# uno_sensor_shield.net
KiCad netlist of a schematic drawn in EAGLE
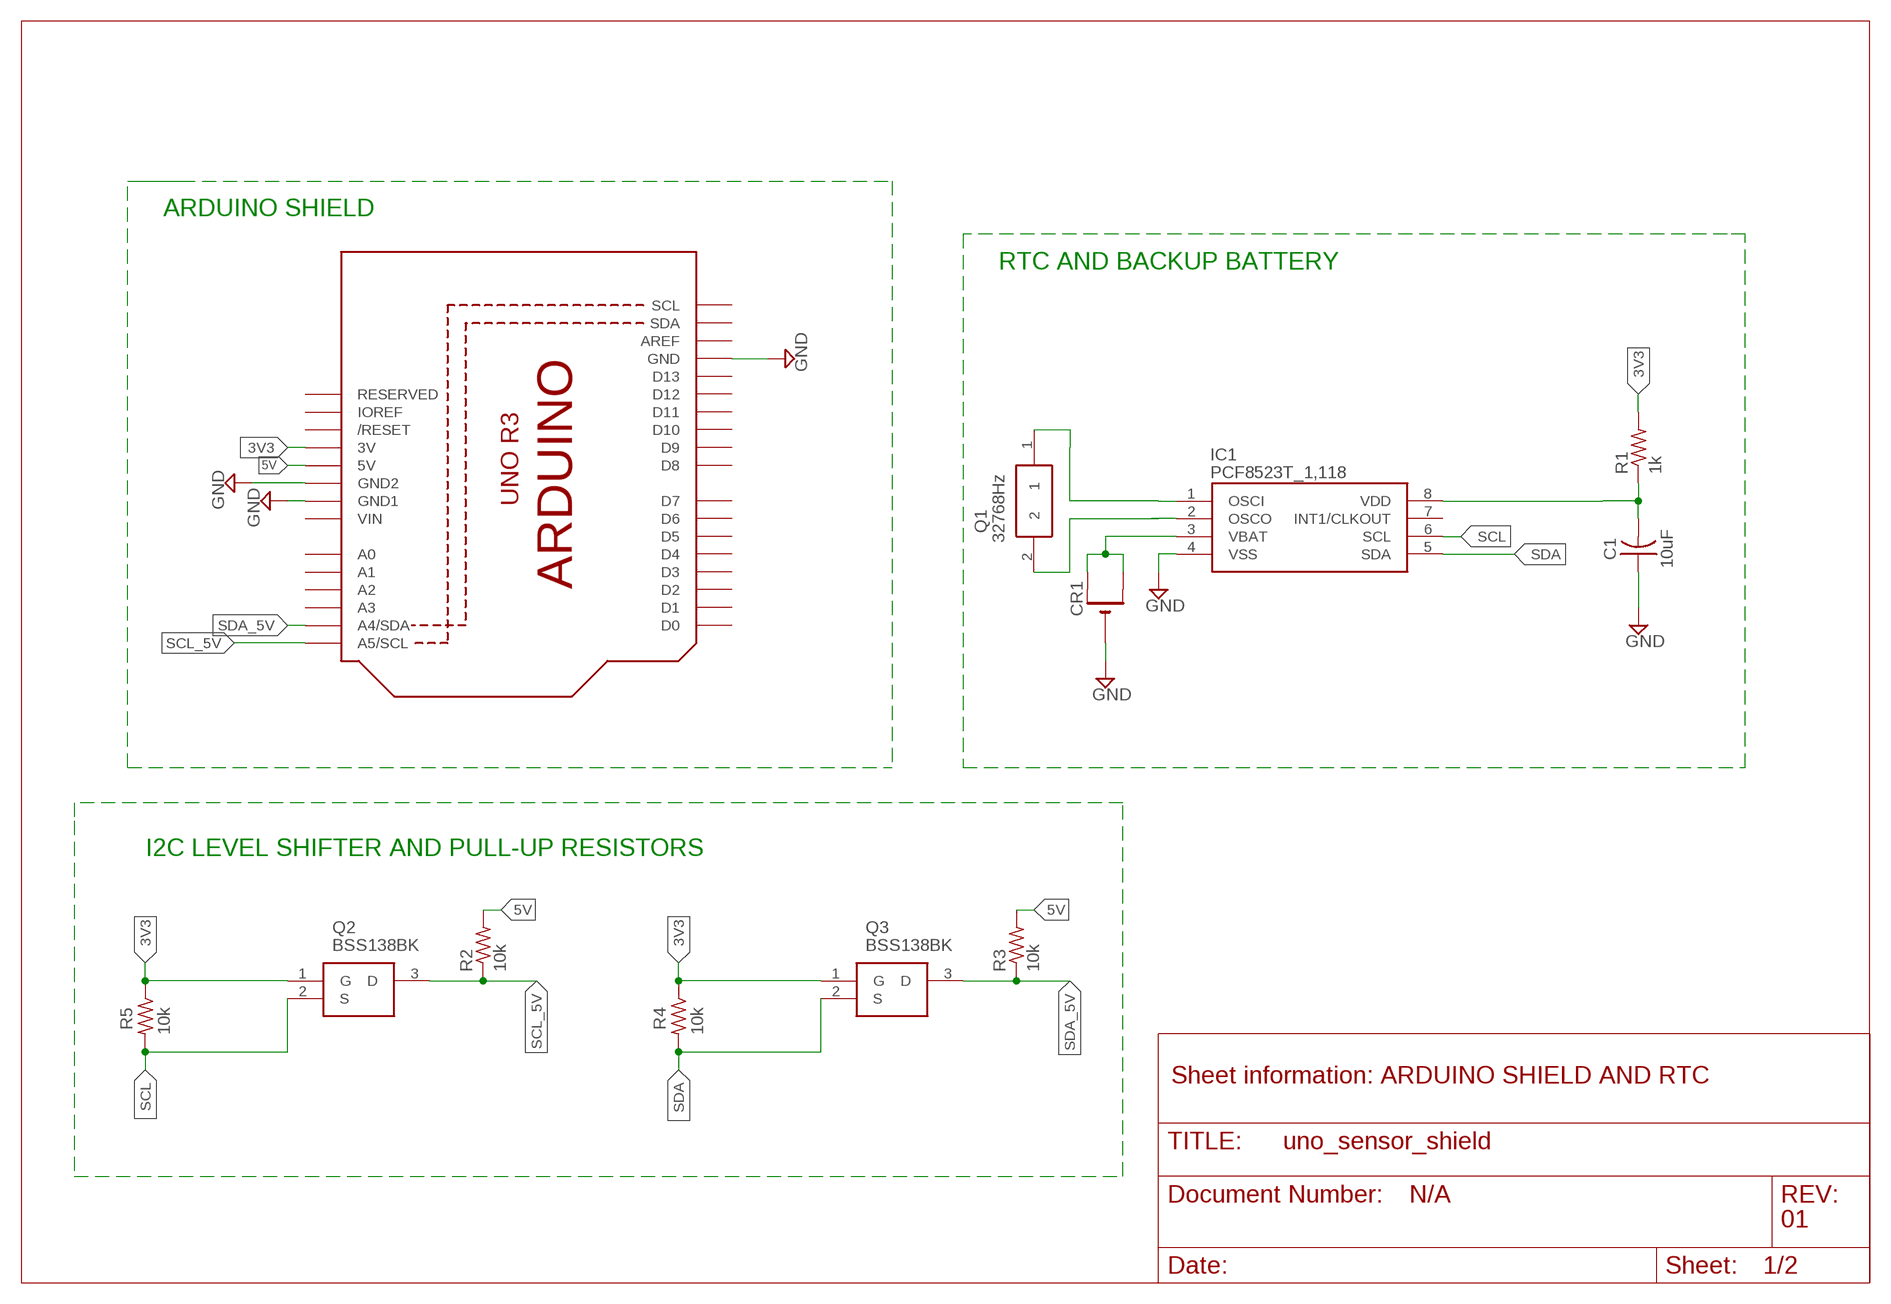
[diagram p0: schematic, sheet 1]
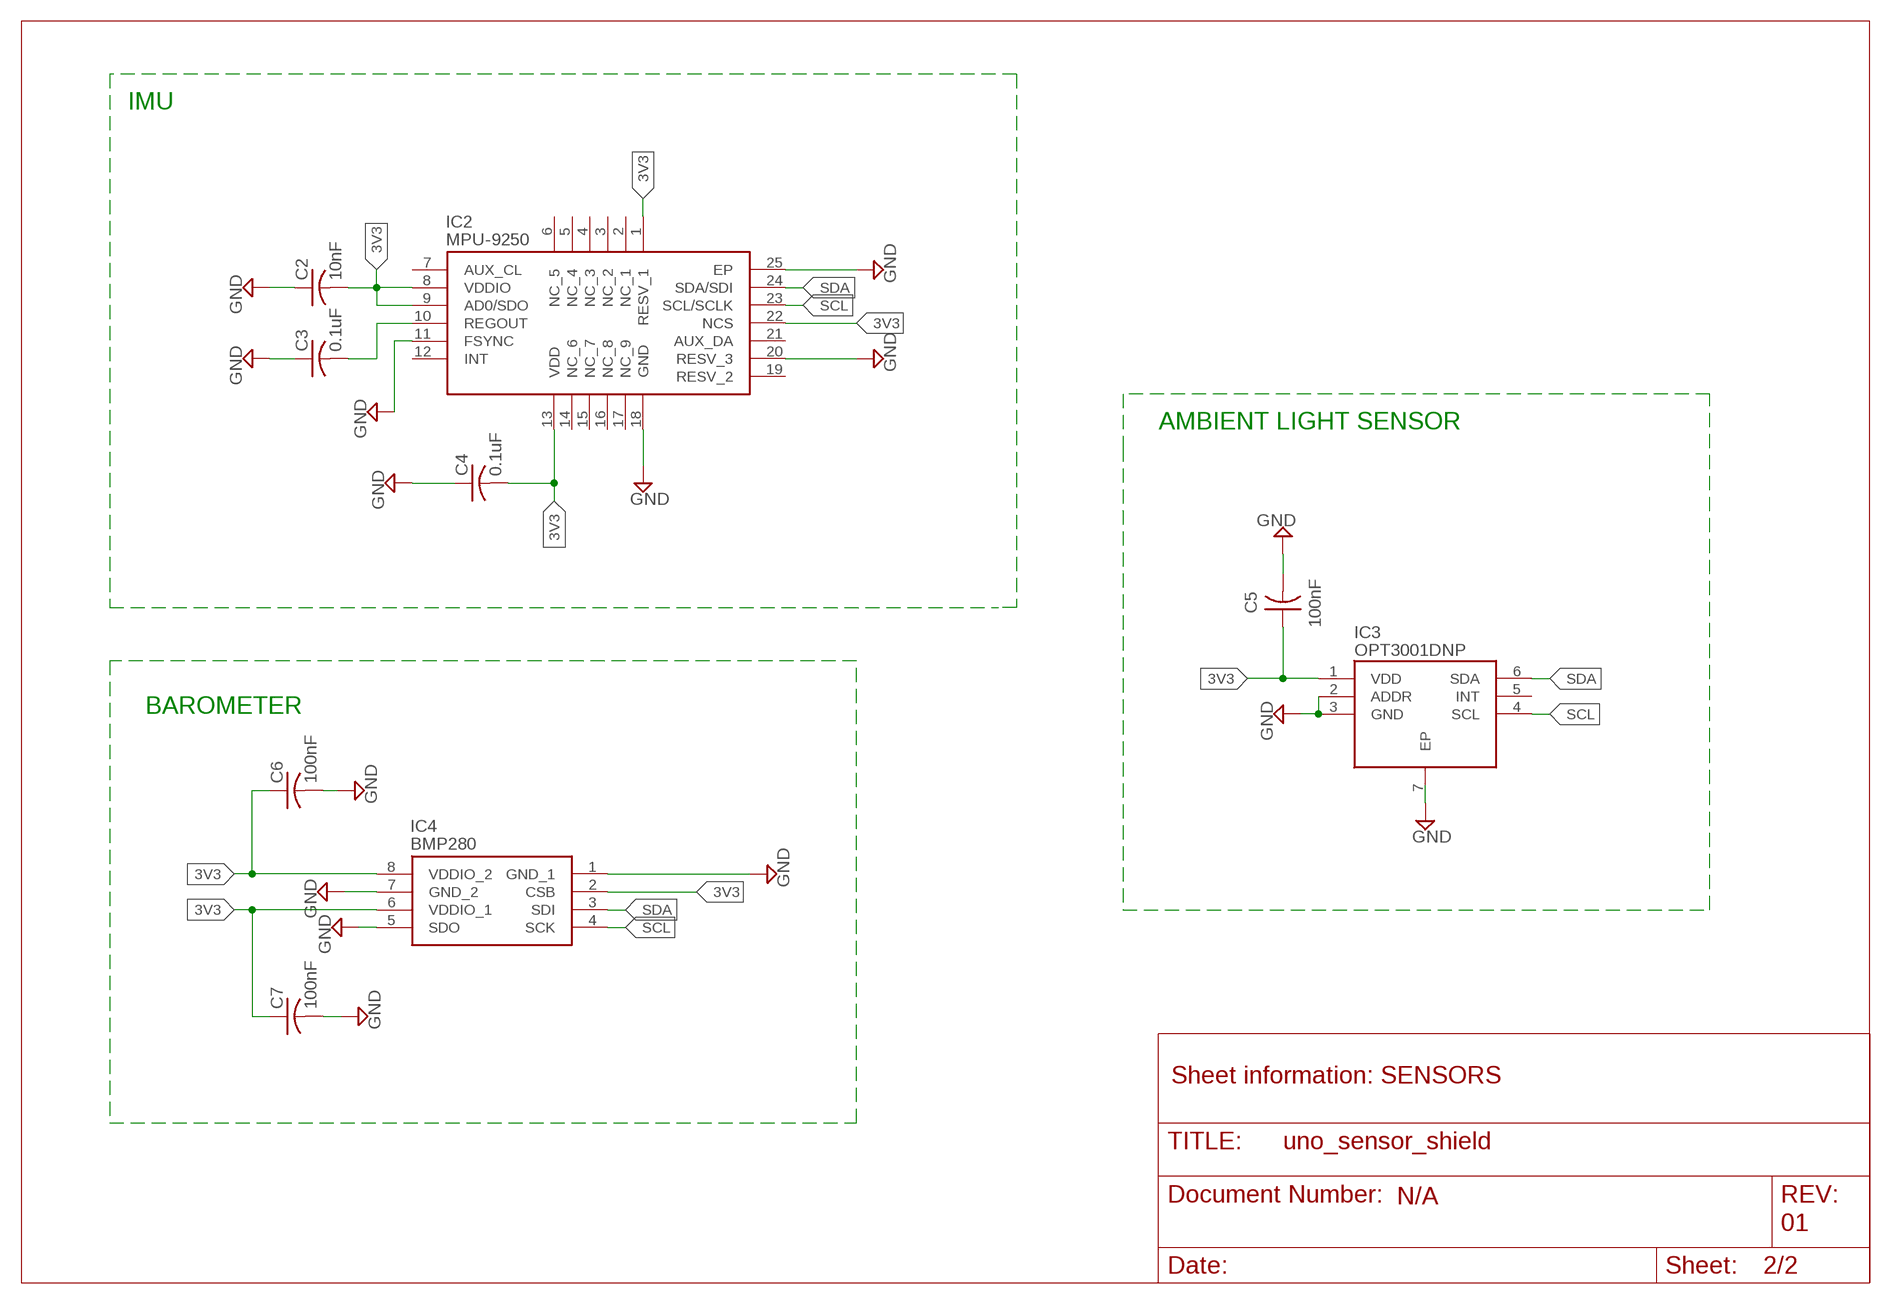
[diagram p1: schematic, sheet 2]

(export (version "E")
  (design (tool "Eeschema 10.0.6"))
  (components
    (comp (ref "C2")
      (value "10nF")
      (footprint "eagle-import:C0805")
      (libsource (lib "eagle-import") (part "C-USC0805"))
    )
    (comp (ref "C3")
      (value "0.1uF")
      (footprint "eagle-import:C0805")
      (libsource (lib "eagle-import") (part "C-USC0805"))
    )
    (comp (ref "C4")
      (value "0.1uF")
      (footprint "eagle-import:C0805")
      (libsource (lib "eagle-import") (part "C-USC0805"))
    )
    (comp (ref "C5")
      (value "100nF")
      (footprint "eagle-import:C0805")
      (libsource (lib "eagle-import") (part "C-USC0805"))
    )
    (comp (ref "C6")
      (value "100nF")
      (footprint "eagle-import:C0805")
      (libsource (lib "eagle-import") (part "C-USC0805"))
    )
    (comp (ref "C7")
      (value "100nF")
      (footprint "eagle-import:C0805")
      (libsource (lib "eagle-import") (part "C-USC0805"))
    )
    (comp (ref "IC2")
      (value "MPU-9250")
      (footprint "eagle-import:QFN40P300X300X105-25N")
      (fields (field (name "RS_PART_NUMBER") "8837942"))
      (libsource (lib "eagle-import") (part "MPU-9250"))
    )
    (comp (ref "IC3")
      (value "OPT3001DNP")
      (footprint "eagle-import:SON65P200X200X65-7N")
      (fields (field (name "RS_PART_NUMBER") "9009810") (field (name "SPICEPREFIX") "X"))
      (libsource (lib "eagle-import") (part "OPT3001DNP"))
    )
    (comp (ref "IC4")
      (value "BMP280")
      (footprint "eagle-import:8-PIN-METAL-LID-LGA")
      (fields (field (name "ARROW_PART_NUMBER") "bmp280"))
      (libsource (lib "eagle-import") (part "BMP280"))
    )
    (comp (ref "C1")
      (value "10uF")
      (footprint "eagle-import:C0805")
      (libsource (lib "eagle-import") (part "C-USC0805"))
    )
    (comp (ref "CR1")
      (value "CR1220SMT")
      (footprint "eagle-import:CR1220-SMD")
      (libsource (lib "eagle-import") (part "CR1220SMT"))
    )
    (comp (ref "IC1")
      (value "PCF8523T_1,118")
      (footprint "eagle-import:SOIC127P600X175-8N")
      (fields (field (name "ARROW_PART_NUMBER") "PCF8523T/1,118"))
      (libsource (lib "eagle-import") (part "PCF8523T_1,118"))
    )
    (comp (ref "Q1")
      (value "32768Hz")
      (footprint "eagle-import:Q0032768JTX21012520T1LF")
      (fields (field (name "ARROW_PART_NUMBER") "Q 0.032768-JTX210-12.5-20-T1-LF"))
      (libsource (lib "eagle-import") (part "Q_0.032768-JTX210-12.5-20-T1-L"))
    )
    (comp (ref "Q2")
      (value "BSS138BK")
      (footprint "eagle-import:SOT95P230X110-3N")
      (fields (field (name "RS_PART_NUMBER") "7920894P"))
      (libsource (lib "eagle-import") (part "BSS138BK"))
    )
    (comp (ref "Q3")
      (value "BSS138BK")
      (footprint "eagle-import:SOT95P230X110-3N")
      (fields (field (name "RS_PART_NUMBER") "7920894P"))
      (libsource (lib "eagle-import") (part "BSS138BK"))
    )
    (comp (ref "R1")
      (value "1k")
      (footprint "eagle-import:R0805")
      (libsource (lib "eagle-import") (part "R-US_R0805"))
    )
    (comp (ref "R2")
      (value "10k")
      (footprint "eagle-import:R0805")
      (libsource (lib "eagle-import") (part "R-US_R0805"))
    )
    (comp (ref "R3")
      (value "10k")
      (footprint "eagle-import:R0805")
      (libsource (lib "eagle-import") (part "R-US_R0805"))
    )
    (comp (ref "R4")
      (value "10k")
      (footprint "eagle-import:R0805")
      (libsource (lib "eagle-import") (part "R-US_R0805"))
    )
    (comp (ref "R5")
      (value "10k")
      (footprint "eagle-import:R0805")
      (libsource (lib "eagle-import") (part "R-US_R0805"))
    )
    (comp (ref "U1")
      (value "ARDUINOR3-DIMENSION")
      (footprint "eagle-import:ARDUINOR3")
      (libsource (lib "eagle-import") (part "ARDUINOR3-DIMENSION"))
    )
  )
  (nets
    (net (code "1") (name "3V3") (class "Default")
      (node (ref "C2") (pin "2") (pinfunction "2_2") (pintype "passive"))
      (node (ref "C4") (pin "2") (pinfunction "2_2") (pintype "passive"))
      (node (ref "C5") (pin "1") (pinfunction "1_1") (pintype "passive"))
      (node (ref "C6") (pin "1") (pinfunction "1_1") (pintype "passive"))
      (node (ref "C7") (pin "1") (pinfunction "1_1") (pintype "passive"))
      (node (ref "IC2") (pin "1") (pinfunction "RESV_1_1") (pintype "bidirectional"))
      (node (ref "IC2") (pin "13") (pinfunction "VDD_13") (pintype "power_in"))
      (node (ref "IC2") (pin "22") (pinfunction "NCS_22") (pintype "input"))
      (node (ref "IC2") (pin "8") (pinfunction "VDDIO_8") (pintype "power_in"))
      (node (ref "IC2") (pin "9") (pinfunction "AD0/SDO_9") (pintype "bidirectional"))
      (node (ref "IC3") (pin "1") (pinfunction "VDD_1") (pintype "power_in"))
      (node (ref "IC4") (pin "2") (pinfunction "CSB_2") (pintype "input"))
      (node (ref "IC4") (pin "6") (pinfunction "VDDIO_1_6") (pintype "power_in"))
      (node (ref "IC4") (pin "8") (pinfunction "VDDIO_2_8") (pintype "power_in"))
      (node (ref "Q2") (pin "1") (pinfunction "G_1") (pintype "bidirectional"))
      (node (ref "Q3") (pin "1") (pinfunction "G_1") (pintype "bidirectional"))
      (node (ref "R1") (pin "2") (pinfunction "2_2") (pintype "passive"))
      (node (ref "R4") (pin "1") (pinfunction "1_1") (pintype "passive"))
      (node (ref "R5") (pin "1") (pinfunction "1_1") (pintype "passive"))
      (node (ref "U1") (pin "3V") (pinfunction "3V_3V") (pintype "power_in"))
    )
    (net (code "2") (name "5V") (class "Default")
      (node (ref "R2") (pin "2") (pinfunction "2_2") (pintype "passive"))
      (node (ref "R3") (pin "2") (pinfunction "2_2") (pintype "passive"))
      (node (ref "U1") (pin "5V") (pinfunction "5V_5V") (pintype "power_in"))
    )
    (net (code "3") (name "GND") (class "Default")
      (node (ref "C1") (pin "1") (pinfunction "1_1") (pintype "passive"))
      (node (ref "C2") (pin "1") (pinfunction "1_1") (pintype "passive"))
      (node (ref "C3") (pin "1") (pinfunction "1_1") (pintype "passive"))
      (node (ref "C4") (pin "1") (pinfunction "1_1") (pintype "passive"))
      (node (ref "C5") (pin "2") (pinfunction "2_2") (pintype "passive"))
      (node (ref "C6") (pin "2") (pinfunction "2_2") (pintype "passive"))
      (node (ref "C7") (pin "2") (pinfunction "2_2") (pintype "passive"))
      (node (ref "CR1") (pin "-") (pinfunction "-_-") (pintype "passive"))
      (node (ref "IC1") (pin "4") (pinfunction "VSS_4") (pintype "bidirectional"))
      (node (ref "IC2") (pin "11") (pinfunction "FSYNC_11") (pintype "bidirectional"))
      (node (ref "IC2") (pin "18") (pinfunction "GND_18") (pintype "power_in"))
      (node (ref "IC2") (pin "20") (pinfunction "RESV_3_20") (pintype "bidirectional"))
      (node (ref "IC2") (pin "25") (pinfunction "EP_25") (pintype "bidirectional"))
      (node (ref "IC3") (pin "2") (pinfunction "ADDR_2") (pintype "bidirectional"))
      (node (ref "IC3") (pin "3") (pinfunction "GND_3") (pintype "power_in"))
      (node (ref "IC3") (pin "7") (pinfunction "EP_7") (pintype "power_in"))
      (node (ref "IC4") (pin "1") (pinfunction "GND_1_1") (pintype "power_in"))
      (node (ref "IC4") (pin "5") (pinfunction "SDO_5") (pintype "bidirectional"))
      (node (ref "IC4") (pin "7") (pinfunction "GND_2_7") (pintype "power_in"))
      (node (ref "U1") (pin "GND") (pinfunction "GND_GND") (pintype "power_in"))
      (node (ref "U1") (pin "GND1") (pinfunction "GND1_GND1") (pintype "power_in"))
      (node (ref "U1") (pin "GND2") (pinfunction "GND2_GND2") (pintype "power_in"))
    )
    (net (code "4") (name "Net-(CR1-+)") (class "Default")
      (node (ref "CR1") (pin "+$1") (pinfunction "+_+$1") (pintype "passive"))
      (node (ref "CR1") (pin "+$2") (pinfunction "+1_+$2") (pintype "passive"))
      (node (ref "IC1") (pin "3") (pinfunction "VBAT_3") (pintype "bidirectional"))
    )
    (net (code "5") (name "Net-(IC1-OSCI)") (class "Default")
      (node (ref "IC1") (pin "1") (pinfunction "OSCI_1") (pintype "bidirectional"))
      (node (ref "Q1") (pin "1") (pinfunction "1_1") (pintype "bidirectional"))
    )
    (net (code "6") (name "Net-(IC1-OSCO)") (class "Default")
      (node (ref "IC1") (pin "2") (pinfunction "OSCO_2") (pintype "bidirectional"))
      (node (ref "Q1") (pin "2") (pinfunction "2_2") (pintype "bidirectional"))
    )
    (net (code "7") (name "Net-(IC1-VDD)") (class "Default")
      (node (ref "C1") (pin "2") (pinfunction "2_2") (pintype "passive"))
      (node (ref "IC1") (pin "8") (pinfunction "VDD_8") (pintype "bidirectional"))
      (node (ref "R1") (pin "1") (pinfunction "1_1") (pintype "passive"))
    )
    (net (code "8") (name "Net-(IC2-REGOUT)") (class "Default")
      (node (ref "C3") (pin "2") (pinfunction "2_2") (pintype "passive"))
      (node (ref "IC2") (pin "10") (pinfunction "REGOUT_10") (pintype "output"))
    )
    (net (code "9") (name "SCL") (class "Default")
      (node (ref "IC1") (pin "6") (pinfunction "SCL_6") (pintype "bidirectional"))
      (node (ref "IC2") (pin "23") (pinfunction "SCL/SCLK_23") (pintype "input"))
      (node (ref "IC3") (pin "4") (pinfunction "SCL_4") (pintype "bidirectional"))
      (node (ref "IC4") (pin "4") (pinfunction "SCK_4") (pintype "bidirectional"))
      (node (ref "Q2") (pin "2") (pinfunction "S_2") (pintype "bidirectional"))
      (node (ref "R5") (pin "2") (pinfunction "2_2") (pintype "passive"))
    )
    (net (code "10") (name "SCL_5V") (class "Default")
      (node (ref "Q2") (pin "3") (pinfunction "D_3") (pintype "bidirectional"))
      (node (ref "R2") (pin "1") (pinfunction "1_1") (pintype "passive"))
      (node (ref "U1") (pin "A5") (pinfunction "A5/SCL_A5") (pintype "bidirectional"))
    )
    (net (code "11") (name "SDA") (class "Default")
      (node (ref "IC1") (pin "5") (pinfunction "SDA_5") (pintype "bidirectional"))
      (node (ref "IC2") (pin "24") (pinfunction "SDA/SDI_24") (pintype "bidirectional"))
      (node (ref "IC3") (pin "6") (pinfunction "SDA_6") (pintype "bidirectional"))
      (node (ref "IC4") (pin "3") (pinfunction "SDI_3") (pintype "bidirectional"))
      (node (ref "Q3") (pin "2") (pinfunction "S_2") (pintype "bidirectional"))
      (node (ref "R4") (pin "2") (pinfunction "2_2") (pintype "passive"))
    )
    (net (code "12") (name "SDA_5V") (class "Default")
      (node (ref "Q3") (pin "3") (pinfunction "D_3") (pintype "bidirectional"))
      (node (ref "R3") (pin "1") (pinfunction "1_1") (pintype "passive"))
      (node (ref "U1") (pin "A4") (pinfunction "A4/SDA_A4") (pintype "bidirectional"))
    )
    (net (code "13") (name "VIN") (class "Default")
      (node (ref "U1") (pin "VIN") (pinfunction "VIN_VIN") (pintype "power_in"))
    )
    (net (code "14") (name "unconnected-(IC1-INT1{slash}CLKOUT-Pad7)") (class "Default")
      (node (ref "IC1") (pin "7") (pinfunction "INT1/CLKOUT_7") (pintype "bidirectional"))
    )
    (net (code "15") (name "unconnected-(IC2-AUX_CL-Pad7)") (class "Default")
      (node (ref "IC2") (pin "7") (pinfunction "AUX_CL_7") (pintype "bidirectional"))
    )
    (net (code "16") (name "unconnected-(IC2-AUX_DA-Pad21)") (class "Default")
      (node (ref "IC2") (pin "21") (pinfunction "AUX_DA_21") (pintype "bidirectional"))
    )
    (net (code "17") (name "unconnected-(IC2-INT-Pad12)") (class "Default")
      (node (ref "IC2") (pin "12") (pinfunction "INT_12") (pintype "input"))
    )
    (net (code "18") (name "unconnected-(IC2-NC_1-Pad2)") (class "Default")
      (node (ref "IC2") (pin "2") (pinfunction "NC_1_2") (pintype "bidirectional"))
    )
    (net (code "19") (name "unconnected-(IC2-NC_2-Pad3)") (class "Default")
      (node (ref "IC2") (pin "3") (pinfunction "NC_2_3") (pintype "bidirectional"))
    )
    (net (code "20") (name "unconnected-(IC2-NC_3-Pad4)") (class "Default")
      (node (ref "IC2") (pin "4") (pinfunction "NC_3_4") (pintype "bidirectional"))
    )
    (net (code "21") (name "unconnected-(IC2-NC_4-Pad5)") (class "Default")
      (node (ref "IC2") (pin "5") (pinfunction "NC_4_5") (pintype "bidirectional"))
    )
    (net (code "22") (name "unconnected-(IC2-NC_5-Pad6)") (class "Default")
      (node (ref "IC2") (pin "6") (pinfunction "NC_5_6") (pintype "bidirectional"))
    )
    (net (code "23") (name "unconnected-(IC2-NC_6-Pad14)") (class "Default")
      (node (ref "IC2") (pin "14") (pinfunction "NC_6_14") (pintype "bidirectional"))
    )
    (net (code "24") (name "unconnected-(IC2-NC_7-Pad15)") (class "Default")
      (node (ref "IC2") (pin "15") (pinfunction "NC_7_15") (pintype "bidirectional"))
    )
    (net (code "25") (name "unconnected-(IC2-NC_8-Pad16)") (class "Default")
      (node (ref "IC2") (pin "16") (pinfunction "NC_8_16") (pintype "bidirectional"))
    )
    (net (code "26") (name "unconnected-(IC2-NC_9-Pad17)") (class "Default")
      (node (ref "IC2") (pin "17") (pinfunction "NC_9_17") (pintype "bidirectional"))
    )
    (net (code "27") (name "unconnected-(IC2-RESV_2-Pad19)") (class "Default")
      (node (ref "IC2") (pin "19") (pinfunction "RESV_2_19") (pintype "bidirectional"))
    )
    (net (code "28") (name "unconnected-(IC3-INT-Pad5)") (class "Default")
      (node (ref "IC3") (pin "5") (pinfunction "INT_5") (pintype "input"))
    )
    (net (code "29") (name "unconnected-(U1-PadA0)") (class "Default")
      (node (ref "U1") (pin "A0") (pinfunction "A0_A0") (pintype "bidirectional"))
    )
    (net (code "30") (name "unconnected-(U1-PadA1)") (class "Default")
      (node (ref "U1") (pin "A1") (pinfunction "A1_A1") (pintype "bidirectional"))
    )
    (net (code "31") (name "unconnected-(U1-PadA2)") (class "Default")
      (node (ref "U1") (pin "A2") (pinfunction "A2_A2") (pintype "bidirectional"))
    )
    (net (code "32") (name "unconnected-(U1-PadA3)") (class "Default")
      (node (ref "U1") (pin "A3") (pinfunction "A3_A3") (pintype "bidirectional"))
    )
    (net (code "33") (name "unconnected-(U1-PadAREF)") (class "Default")
      (node (ref "U1") (pin "AREF") (pinfunction "AREF_AREF") (pintype "bidirectional"))
    )
    (net (code "34") (name "unconnected-(U1-PadD0)") (class "Default")
      (node (ref "U1") (pin "D0") (pinfunction "D0_D0") (pintype "bidirectional"))
    )
    (net (code "35") (name "unconnected-(U1-PadD1)") (class "Default")
      (node (ref "U1") (pin "D1") (pinfunction "D1_D1") (pintype "bidirectional"))
    )
    (net (code "36") (name "unconnected-(U1-PadD2)") (class "Default")
      (node (ref "U1") (pin "D2") (pinfunction "D2_D2") (pintype "bidirectional"))
    )
    (net (code "37") (name "unconnected-(U1-PadD3)") (class "Default")
      (node (ref "U1") (pin "D3") (pinfunction "D3_D3") (pintype "bidirectional"))
    )
    (net (code "38") (name "unconnected-(U1-PadD4)") (class "Default")
      (node (ref "U1") (pin "D4") (pinfunction "D4_D4") (pintype "bidirectional"))
    )
    (net (code "39") (name "unconnected-(U1-PadD5)") (class "Default")
      (node (ref "U1") (pin "D5") (pinfunction "D5_D5") (pintype "bidirectional"))
    )
    (net (code "40") (name "unconnected-(U1-PadD6)") (class "Default")
      (node (ref "U1") (pin "D6") (pinfunction "D6_D6") (pintype "bidirectional"))
    )
    (net (code "41") (name "unconnected-(U1-PadD7)") (class "Default")
      (node (ref "U1") (pin "D7") (pinfunction "D7_D7") (pintype "bidirectional"))
    )
    (net (code "42") (name "unconnected-(U1-PadD8)") (class "Default")
      (node (ref "U1") (pin "D8") (pinfunction "D8_D8") (pintype "bidirectional"))
    )
    (net (code "43") (name "unconnected-(U1-PadD9)") (class "Default")
      (node (ref "U1") (pin "D9") (pinfunction "D9_D9") (pintype "bidirectional"))
    )
    (net (code "44") (name "unconnected-(U1-PadD10)") (class "Default")
      (node (ref "U1") (pin "D10") (pinfunction "D10_D10") (pintype "bidirectional"))
    )
    (net (code "45") (name "unconnected-(U1-PadD11)") (class "Default")
      (node (ref "U1") (pin "D11") (pinfunction "D11_D11") (pintype "bidirectional"))
    )
    (net (code "46") (name "unconnected-(U1-PadD12)") (class "Default")
      (node (ref "U1") (pin "D12") (pinfunction "D12_D12") (pintype "bidirectional"))
    )
    (net (code "47") (name "unconnected-(U1-PadD13)") (class "Default")
      (node (ref "U1") (pin "D13") (pinfunction "D13_D13") (pintype "bidirectional"))
    )
    (net (code "48") (name "unconnected-(U1-PadIOREF)") (class "Default")
      (node (ref "U1") (pin "IOREF") (pinfunction "IOREF_IOREF") (pintype "output"))
    )
    (net (code "49") (name "unconnected-(U1-PadRESERVED)") (class "Default")
      (node (ref "U1") (pin "RESERVED") (pinfunction "RESERVED_RESERVED") (pintype "no_connect"))
    )
    (net (code "50") (name "unconnected-(U1-PadSCL)") (class "Default")
      (node (ref "U1") (pin "SCL") (pinfunction "SCL_SCL") (pintype "bidirectional"))
    )
    (net (code "51") (name "unconnected-(U1-PadSDA)") (class "Default")
      (node (ref "U1") (pin "SDA") (pinfunction "SDA_SDA") (pintype "bidirectional"))
    )
    (net (code "52") (name "unconnected-(U1-{slash}RESET-PadRESET)") (class "Default")
      (node (ref "U1") (pin "RESET") (pinfunction "/RESET_RESET") (pintype "bidirectional"))
    )
  )
)
